# Condor2_ESC.net
KiCad netlist of a schematic drawn in Altium Designer
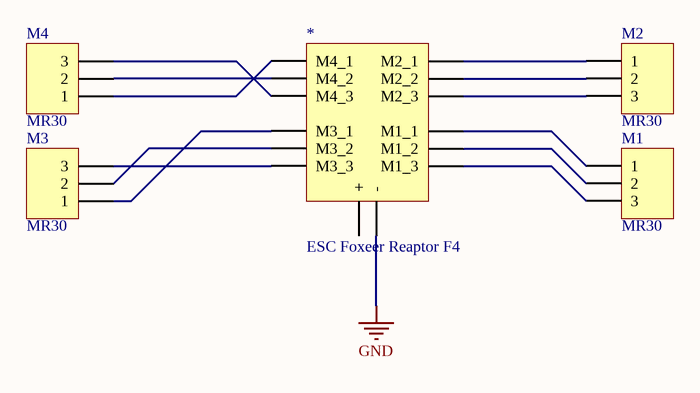
[diagram p0: Condor2_ESC.SchDoc]

(export (version "E")
  (design (tool "Eeschema 10.0.6"))
  (components
    (comp (ref "*")
      (value "ESC Foxeer Reaptor F4")
      (footprint "FOXEeR REAPER")
      (libsource (lib "CB_REV_C") (part "ESC Foxeer Reaptor F4"))
    )
    (comp (ref "M1")
      (value "MR30")
      (footprint "MR30")
      (fields (field (name "PUBLISHER") "Altium Limited"))
      (libsource (lib "CB_REV_C") (part "MR30"))
    )
    (comp (ref "M2")
      (value "MR30")
      (footprint "MR30")
      (fields (field (name "PUBLISHER") "Altium Limited"))
      (libsource (lib "CB_REV_C") (part "MR30"))
    )
    (comp (ref "M3")
      (value "MR30")
      (footprint "MR30")
      (fields (field (name "PUBLISHER") "Altium Limited"))
      (libsource (lib "") (part "MR30_1"))
    )
    (comp (ref "M4")
      (value "MR30")
      (footprint "MR30")
      (fields (field (name "PUBLISHER") "Altium Limited"))
      (libsource (lib "") (part "MR30_1"))
    )
  )
  (nets
    (net (code "1") (name "GND") (class "Default")
      (node (ref "*") (pin "8") (pinfunction "-_8") (pintype "passive"))
    )
    (net (code "2") (name "Net-(*-M1_1)") (class "Default")
      (node (ref "*") (pin "11") (pinfunction "M1_1_11") (pintype "passive"))
      (node (ref "M1") (pin "1") (pinfunction "1_1") (pintype "passive"))
    )
    (net (code "3") (name "Net-(*-M1_2)") (class "Default")
      (node (ref "*") (pin "10") (pinfunction "M1_2_10") (pintype "passive"))
      (node (ref "M1") (pin "2") (pinfunction "2_2") (pintype "passive"))
    )
    (net (code "4") (name "Net-(*-M1_3)") (class "Default")
      (node (ref "*") (pin "9") (pinfunction "M1_3_9") (pintype "passive"))
      (node (ref "M1") (pin "3") (pinfunction "3_3") (pintype "passive"))
    )
    (net (code "5") (name "Net-(*-M2_1)") (class "Default")
      (node (ref "*") (pin "14") (pinfunction "M2_1_14") (pintype "passive"))
      (node (ref "M2") (pin "1") (pinfunction "1_1") (pintype "passive"))
    )
    (net (code "6") (name "Net-(*-M2_2)") (class "Default")
      (node (ref "*") (pin "13") (pinfunction "M2_2_13") (pintype "passive"))
      (node (ref "M2") (pin "2") (pinfunction "2_2") (pintype "passive"))
    )
    (net (code "7") (name "Net-(*-M2_3)") (class "Default")
      (node (ref "*") (pin "12") (pinfunction "M2_3_12") (pintype "passive"))
      (node (ref "M2") (pin "3") (pinfunction "3_3") (pintype "passive"))
    )
    (net (code "8") (name "Net-(*-M3_1)") (class "Default")
      (node (ref "*") (pin "4") (pinfunction "M3_1_4") (pintype "passive"))
      (node (ref "M3") (pin "1") (pinfunction "1_1") (pintype "passive"))
    )
    (net (code "9") (name "Net-(*-M3_2)") (class "Default")
      (node (ref "*") (pin "5") (pinfunction "M3_2_5") (pintype "passive"))
      (node (ref "M3") (pin "2") (pinfunction "2_2") (pintype "passive"))
    )
    (net (code "10") (name "Net-(*-M3_3)") (class "Default")
      (node (ref "*") (pin "6") (pinfunction "M3_3_6") (pintype "passive"))
      (node (ref "M3") (pin "3") (pinfunction "3_3") (pintype "passive"))
    )
    (net (code "11") (name "Net-(*-M4_1)") (class "Default")
      (node (ref "*") (pin "1") (pinfunction "M4_1_1") (pintype "passive"))
      (node (ref "M4") (pin "1") (pinfunction "1_1") (pintype "passive"))
    )
    (net (code "12") (name "Net-(*-M4_2)") (class "Default")
      (node (ref "*") (pin "2") (pinfunction "M4_2_2") (pintype "passive"))
      (node (ref "M4") (pin "2") (pinfunction "2_2") (pintype "passive"))
    )
    (net (code "13") (name "Net-(*-M4_3)") (class "Default")
      (node (ref "*") (pin "3") (pinfunction "M4_3_3") (pintype "passive"))
      (node (ref "M4") (pin "3") (pinfunction "3_3") (pintype "passive"))
    )
    (net (code "14") (name "unconnected-(*-+-Pad7)") (class "Default")
      (node (ref "*") (pin "7") (pinfunction "+_7") (pintype "passive"))
    )
  )
)
